# CAN_TOF.net
KiCad netlist of a schematic drawn in EAGLE
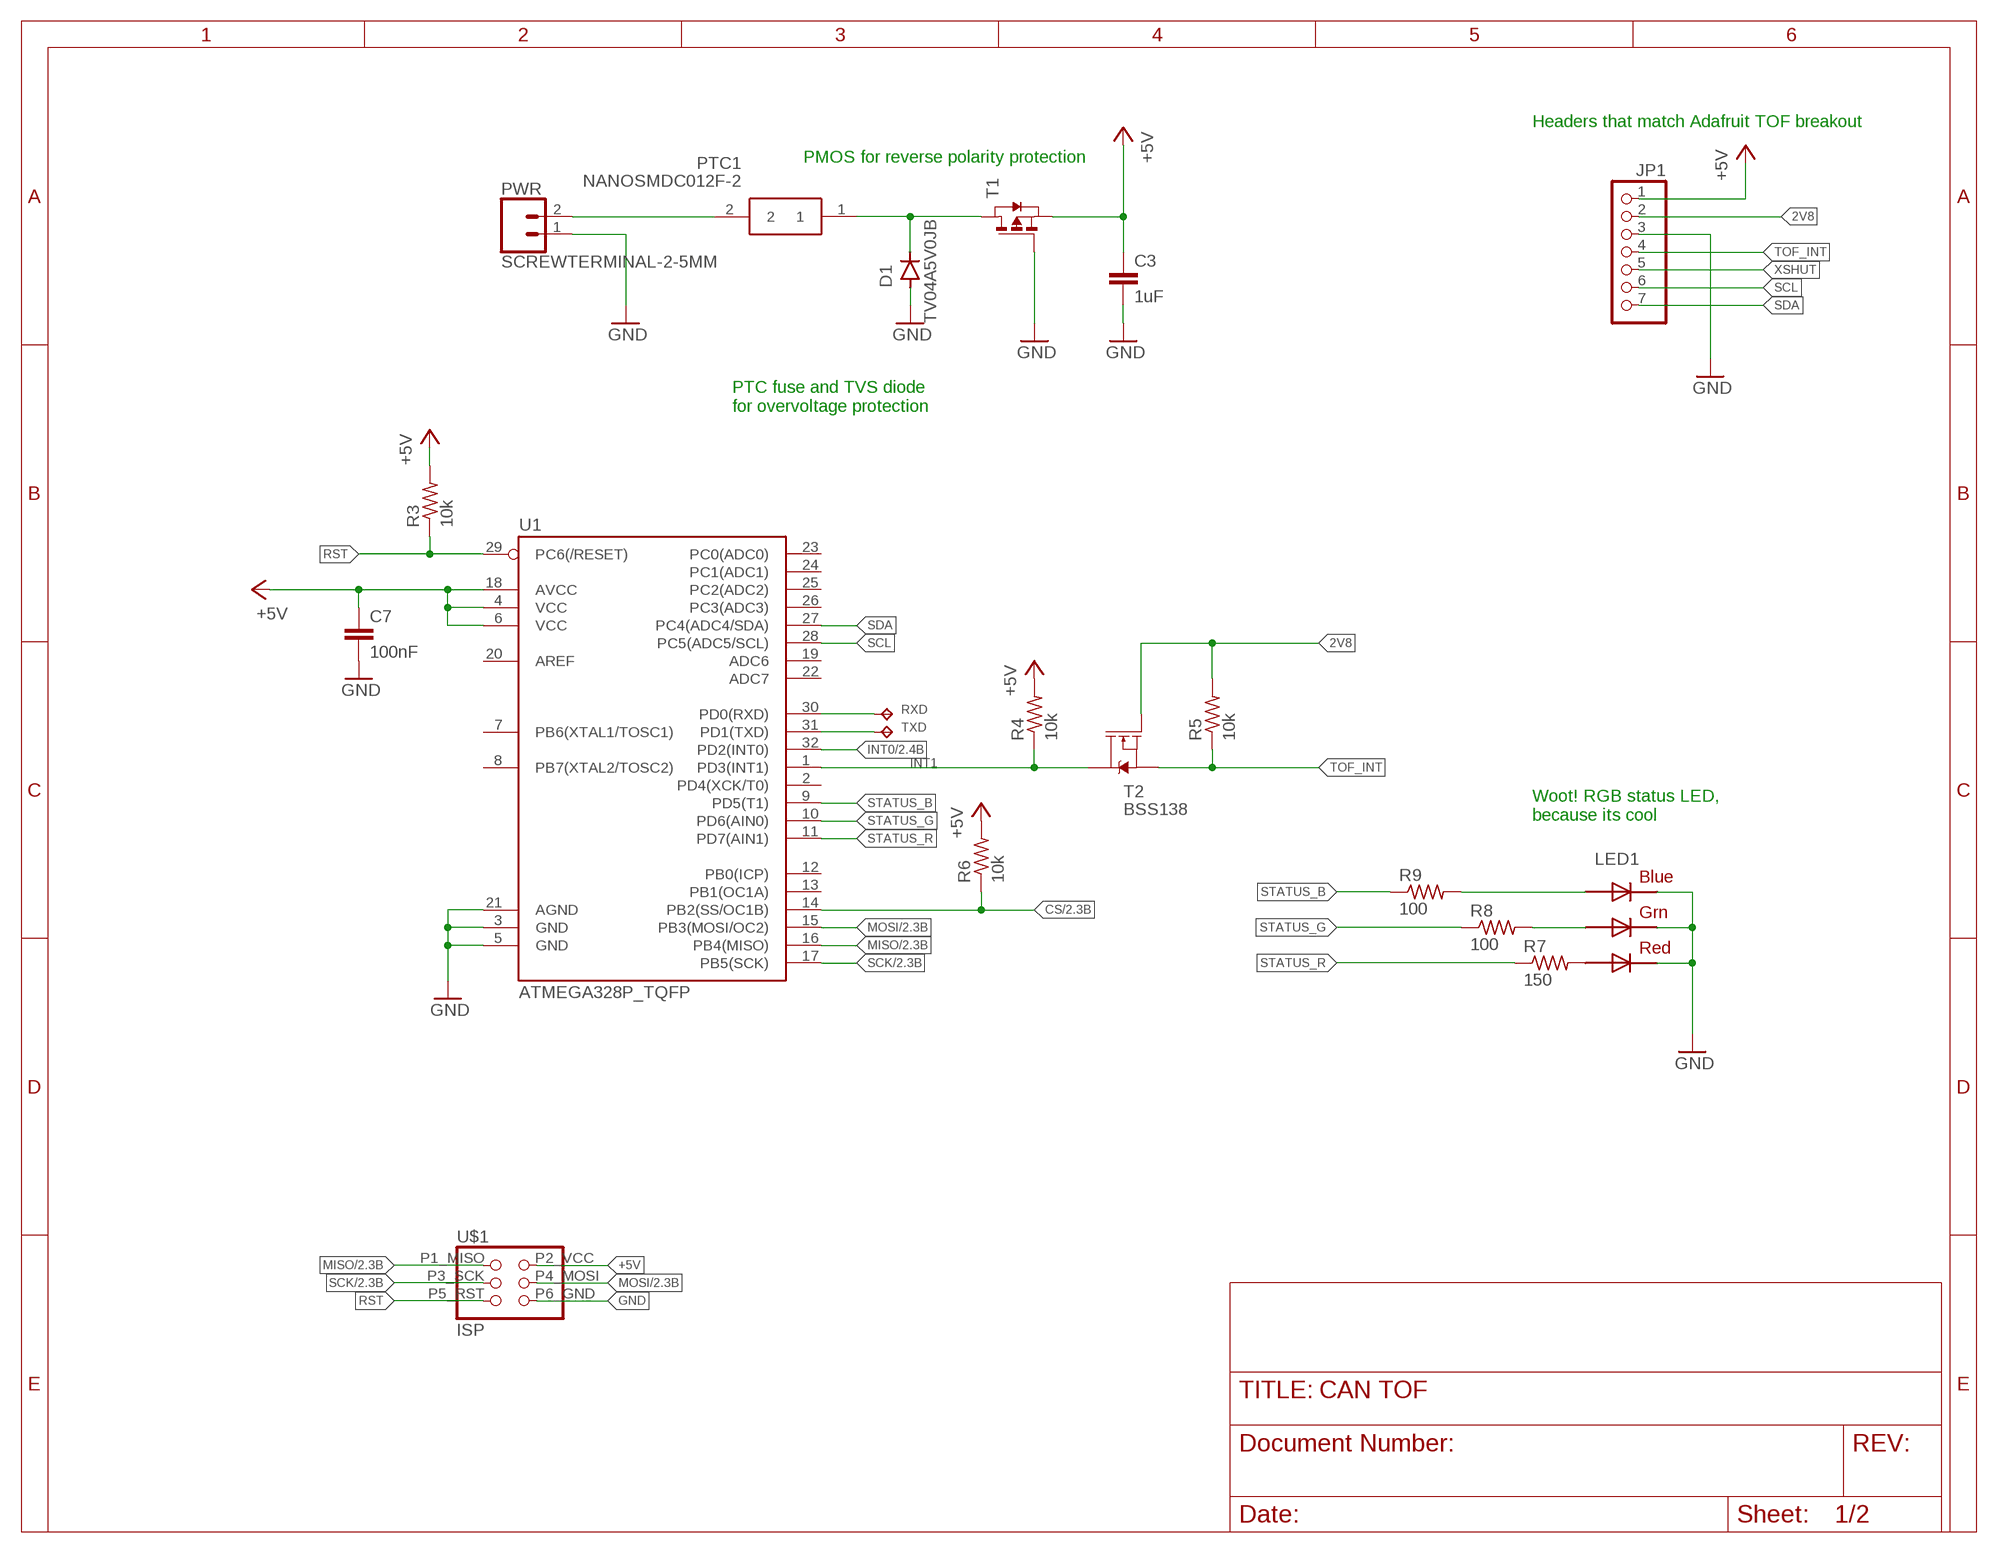
[diagram p0: schematic, sheet 1]
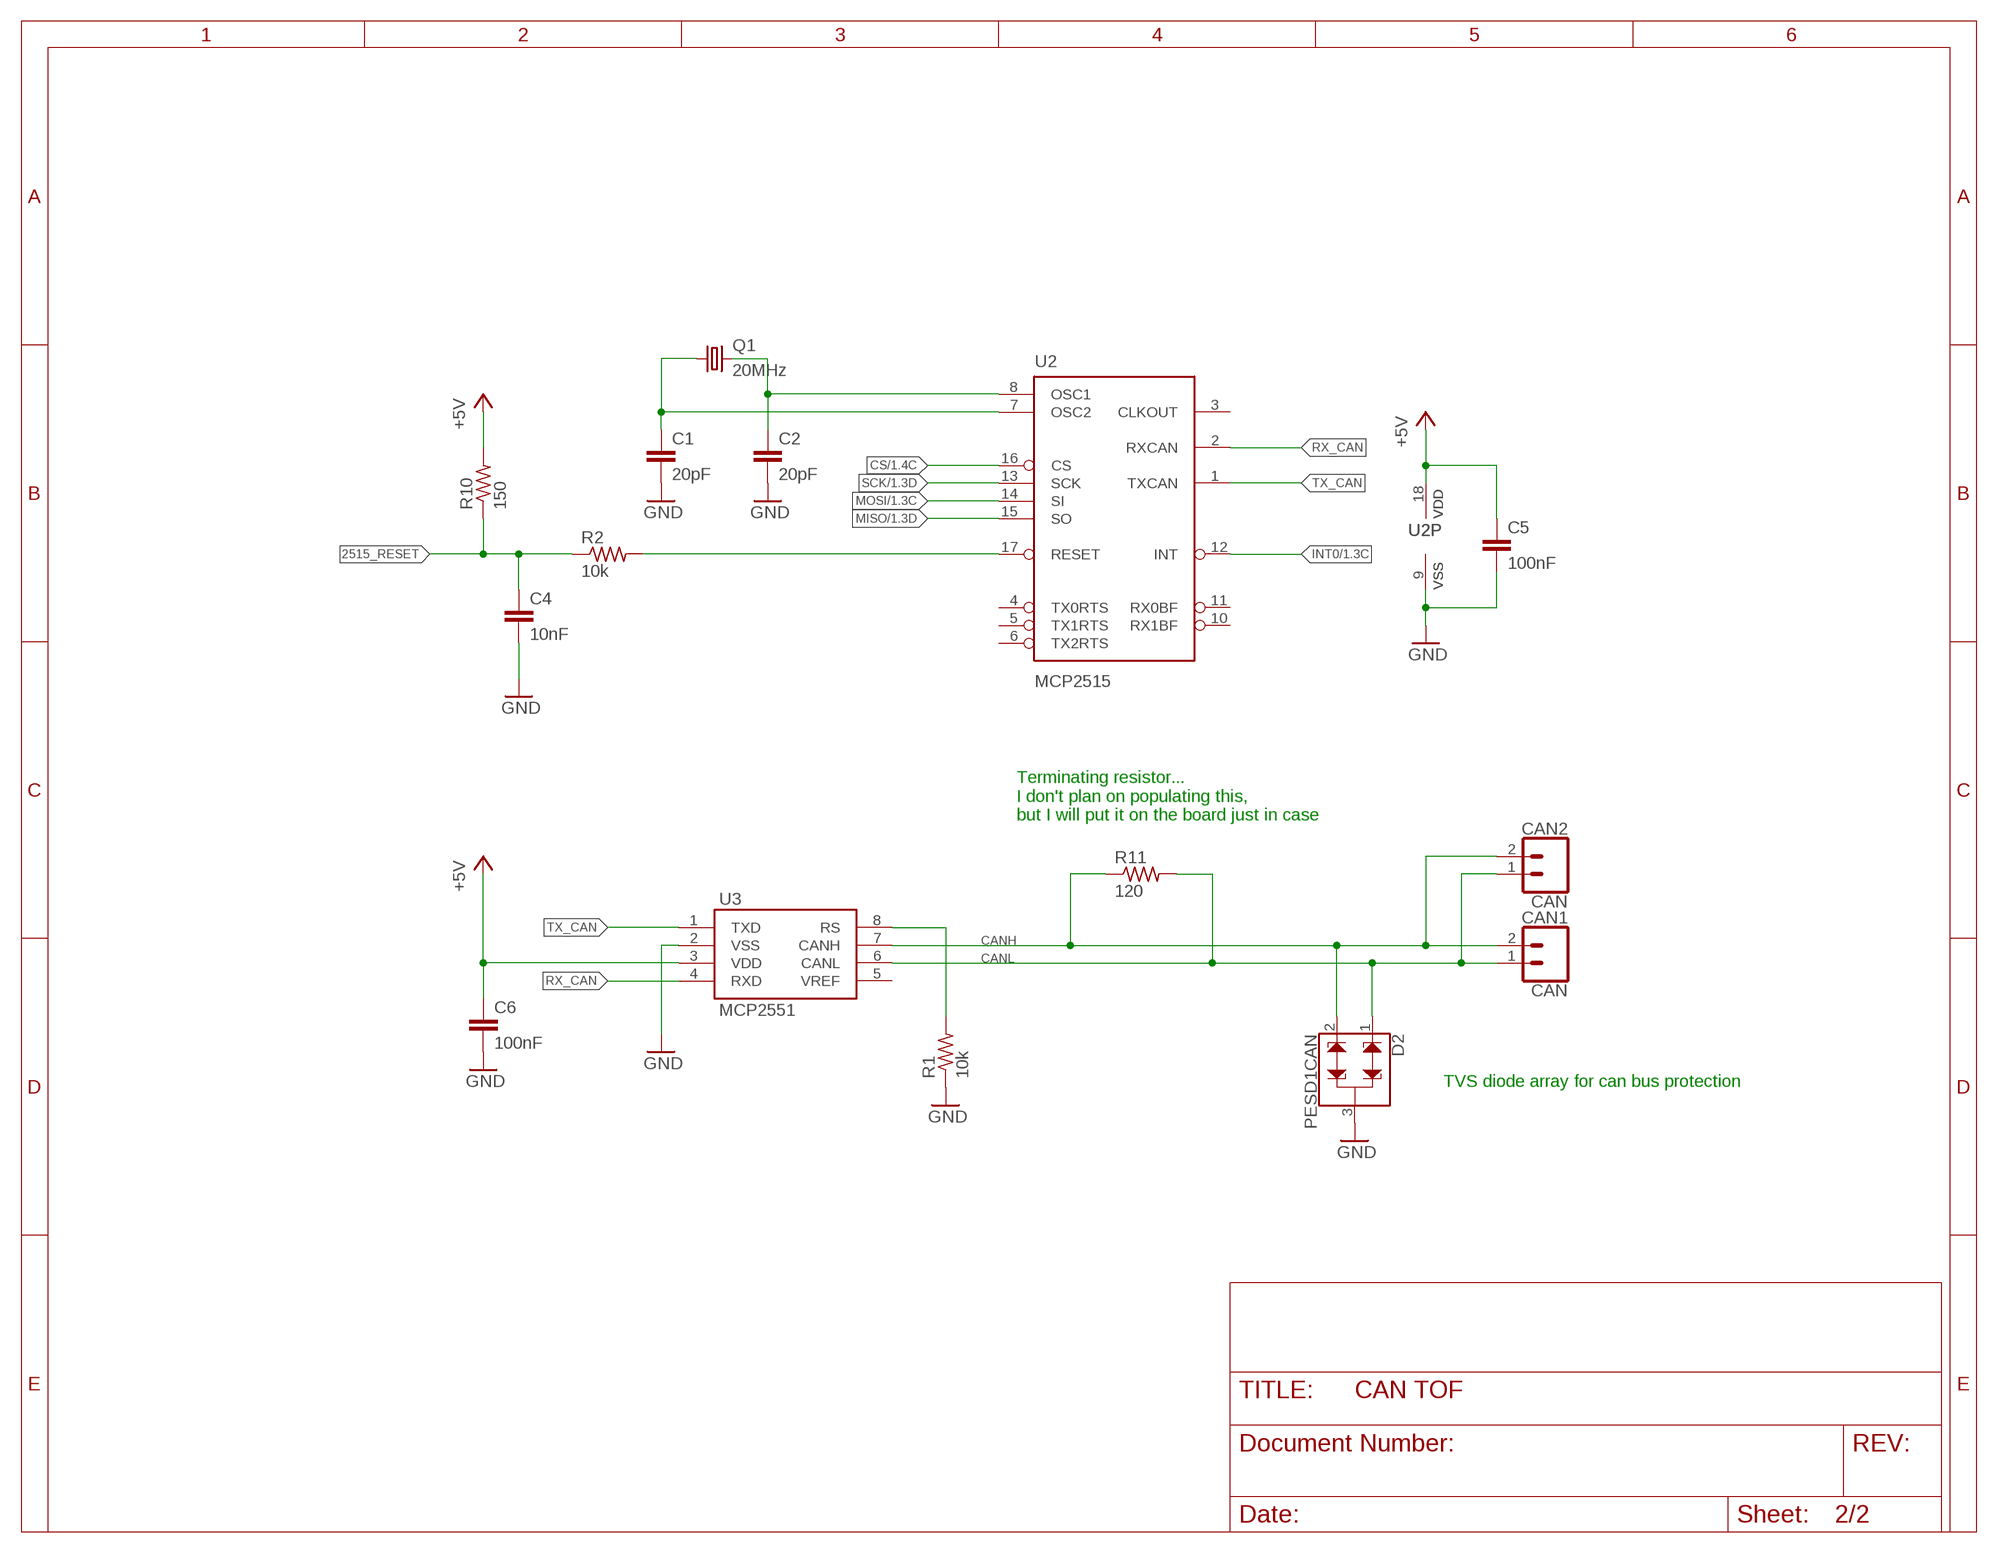
[diagram p1: schematic, sheet 2]

(export (version "E")
  (design (tool "Eeschema 10.0.6"))
  (components
    (comp (ref "C1")
      (value "20pF")
      (footprint "eagle-import:C0402")
      (libsource (lib "eagle-import") (part "C-EUC0402"))
    )
    (comp (ref "C2")
      (value "20pF")
      (footprint "eagle-import:C0402")
      (libsource (lib "eagle-import") (part "C-EUC0402"))
    )
    (comp (ref "C4")
      (value "10nF")
      (footprint "eagle-import:C0402")
      (libsource (lib "eagle-import") (part "C-EUC0402"))
    )
    (comp (ref "C5")
      (value "100nF")
      (footprint "eagle-import:C0402")
      (libsource (lib "eagle-import") (part "C-EUC0402"))
    )
    (comp (ref "C6")
      (value "100nF")
      (footprint "eagle-import:C0402")
      (libsource (lib "eagle-import") (part "C-EUC0402"))
    )
    (comp (ref "CAN1")
      (value "CAN")
      (footprint "eagle-import:SCREWTERMINAL-5MM-2")
      (libsource (lib "eagle-import") (part "SCREWTERMINAL-2-5MM"))
    )
    (comp (ref "CAN2")
      (value "CAN")
      (footprint "eagle-import:SCREWTERMINAL-5MM-2")
      (libsource (lib "eagle-import") (part "SCREWTERMINAL-2-5MM"))
    )
    (comp (ref "D2")
      (value "PESD1CAN")
      (footprint "eagle-import:SOT23-3")
      (libsource (lib "eagle-import") (part "PESD1CAN"))
    )
    (comp (ref "Q1")
      (value "20MHz")
      (footprint "eagle-import:CTS406")
      (libsource (lib "eagle-import") (part "CRYSTALCTS406"))
    )
    (comp (ref "R1")
      (value "10k")
      (footprint "eagle-import:R0805")
      (libsource (lib "eagle-import") (part "R-US_R0805"))
    )
    (comp (ref "R2")
      (value "10k")
      (footprint "eagle-import:R0805")
      (libsource (lib "eagle-import") (part "R-US_R0805"))
    )
    (comp (ref "R10")
      (value "150")
      (footprint "eagle-import:R0805")
      (libsource (lib "eagle-import") (part "R-US_R0805"))
    )
    (comp (ref "R11")
      (value "120")
      (footprint "eagle-import:R0805")
      (libsource (lib "eagle-import") (part "R-US_R0805"))
    )
    (comp (ref "U2")
      (value "MCP2515")
      (footprint "eagle-import:SO18W")
      (libsource (lib "eagle-import") (part "MCP2515(MCP2510)SO"))
    )
    (comp (ref "U3")
      (value "MCP2551")
      (footprint "eagle-import:SO08")
      (libsource (lib "eagle-import") (part "MCP2551"))
    )
    (comp (ref "C3")
      (value "1uF")
      (footprint "eagle-import:C0805")
      (libsource (lib "eagle-import") (part "C-EUC0805"))
    )
    (comp (ref "C7")
      (value "100nF")
      (footprint "eagle-import:C0402")
      (libsource (lib "eagle-import") (part "C-EUC0402"))
    )
    (comp (ref "D1")
      (value "TV04A5V0JB")
      (footprint "eagle-import:SMA-DO214AC")
      (libsource (lib "eagle-import") (part "GF1"))
    )
    (comp (ref "JP1")
      (value "PINHD-1X7")
      (footprint "eagle-import:1X07")
      (libsource (lib "eagle-import") (part "PINHD-1X7"))
    )
    (comp (ref "LED1")
      (value "RGBLED5050")
      (footprint "eagle-import:RGBLED5050")
      (libsource (lib "eagle-import") (part "RGBLED5050"))
    )
    (comp (ref "PTC1")
      (value "NANOSMDC012F-2")
      (footprint "eagle-import:FUSC3216X100N")
      (fields
        (field (name "MANUFACTURER_PART_NUMBER") "NANOSMDC010F-2")
        (field (name "MOUSER_PART_NUMBER") "650-NANOSMDC010F-2")
      )
      (libsource (lib "eagle-import") (part "NANOSMDC010F-2"))
    )
    (comp (ref "PWR")
      (value "SCREWTERMINAL-2-5MM")
      (footprint "eagle-import:SCREWTERMINAL-5MM-2")
      (libsource (lib "eagle-import") (part "SCREWTERMINAL-2-5MM"))
    )
    (comp (ref "R3")
      (value "10k")
      (footprint "eagle-import:R0805")
      (libsource (lib "eagle-import") (part "R-US_R0805"))
    )
    (comp (ref "R4")
      (value "10k")
      (footprint "eagle-import:R0805")
      (libsource (lib "eagle-import") (part "R-US_R0805"))
    )
    (comp (ref "R5")
      (value "10k")
      (footprint "eagle-import:R0805")
      (libsource (lib "eagle-import") (part "R-US_R0805"))
    )
    (comp (ref "R6")
      (value "10k")
      (footprint "eagle-import:R0805")
      (libsource (lib "eagle-import") (part "R-US_R0805"))
    )
    (comp (ref "R7")
      (value "150")
      (footprint "eagle-import:R0805")
      (libsource (lib "eagle-import") (part "R-US_R0805"))
    )
    (comp (ref "R8")
      (value "100")
      (footprint "eagle-import:R0805")
      (libsource (lib "eagle-import") (part "R-US_R0805"))
    )
    (comp (ref "R9")
      (value "100")
      (footprint "eagle-import:R0805")
      (libsource (lib "eagle-import") (part "R-US_R0805"))
    )
    (comp (ref "RXD")
      (value "TPB1,27")
      (footprint "eagle-import:B1,27")
      (libsource (lib "eagle-import") (part "TPB1,27"))
    )
    (comp (ref "T1")
      (value "PMOSSOT23")
      (footprint "eagle-import:SOT-23")
      (libsource (lib "eagle-import") (part "PMOSSOT23"))
    )
    (comp (ref "T2")
      (value "BSS138")
      (footprint "eagle-import:SOT23-3")
      (libsource (lib "eagle-import") (part "MOSFET-NCH-BSS138"))
    )
    (comp (ref "TXD")
      (value "TPB1,27")
      (footprint "eagle-import:B1,27")
      (libsource (lib "eagle-import") (part "TPB1,27"))
    )
    (comp (ref "U$1")
      (value "ISP")
      (footprint "eagle-import:ISP")
      (libsource (lib "eagle-import") (part "ISP"))
    )
    (comp (ref "U1")
      (value "ATMEGA328P_TQFP")
      (footprint "eagle-import:TQFP32-08")
      (libsource (lib "eagle-import") (part "ATMEGA328P_TQFP"))
    )
  )
  (nets
    (net (code "1") (name "+5V") (class "Default")
      (node (ref "C3") (pin "1") (pinfunction "1_1") (pintype "passive"))
      (node (ref "C5") (pin "1") (pinfunction "1_1") (pintype "passive"))
      (node (ref "C6") (pin "1") (pinfunction "1_1") (pintype "passive"))
      (node (ref "C7") (pin "1") (pinfunction "1_1") (pintype "passive"))
      (node (ref "JP1") (pin "1") (pinfunction "1_1") (pintype "passive"))
      (node (ref "R10") (pin "2") (pinfunction "2_2") (pintype "passive"))
      (node (ref "R3") (pin "2") (pinfunction "2_2") (pintype "passive"))
      (node (ref "R4") (pin "2") (pinfunction "2_2") (pintype "passive"))
      (node (ref "R6") (pin "2") (pinfunction "2_2") (pintype "passive"))
      (node (ref "T1") (pin "2") (pinfunction "S_2") (pintype "passive"))
      (node (ref "U$1") (pin "P2_VCC") (pinfunction "VCC_P2_VCC") (pintype "passive"))
      (node (ref "U1") (pin "18") (pinfunction "AVCC_18") (pintype "bidirectional"))
      (node (ref "U1") (pin "4") (pinfunction "VCC_4") (pintype "bidirectional"))
      (node (ref "U1") (pin "6") (pinfunction "VCC_6") (pintype "bidirectional"))
      (node (ref "U2") (pin "18") (pinfunction "VDD_18") (pintype "power_in"))
      (node (ref "U3") (pin "3") (pinfunction "VDD_3") (pintype "bidirectional"))
    )
    (net (code "2") (name "2V8") (class "Default")
      (node (ref "JP1") (pin "2") (pinfunction "2_2") (pintype "passive"))
      (node (ref "R5") (pin "2") (pinfunction "2_2") (pintype "passive"))
      (node (ref "T2") (pin "1") (pinfunction "G_1") (pintype "bidirectional"))
    )
    (net (code "3") (name "2515_RESET") (class "Default")
      (node (ref "C4") (pin "1") (pinfunction "1_1") (pintype "passive"))
      (node (ref "R10") (pin "1") (pinfunction "1_1") (pintype "passive"))
      (node (ref "R2") (pin "1") (pinfunction "1_1") (pintype "passive"))
    )
    (net (code "4") (name "CANH") (class "Default")
      (node (ref "CAN1") (pin "2") (pinfunction "2_2") (pintype "passive"))
      (node (ref "CAN2") (pin "2") (pinfunction "2_2") (pintype "passive"))
      (node (ref "D2") (pin "2") (pinfunction "2_2") (pintype "bidirectional"))
      (node (ref "R11") (pin "1") (pinfunction "1_1") (pintype "passive"))
      (node (ref "U3") (pin "7") (pinfunction "CANH_7") (pintype "bidirectional"))
    )
    (net (code "5") (name "CANL") (class "Default")
      (node (ref "CAN1") (pin "1") (pinfunction "1_1") (pintype "passive"))
      (node (ref "CAN2") (pin "1") (pinfunction "1_1") (pintype "passive"))
      (node (ref "D2") (pin "1") (pinfunction "1_1") (pintype "bidirectional"))
      (node (ref "R11") (pin "2") (pinfunction "2_2") (pintype "passive"))
      (node (ref "U3") (pin "6") (pinfunction "CANL_6") (pintype "bidirectional"))
    )
    (net (code "6") (name "CS") (class "Default")
      (node (ref "R6") (pin "1") (pinfunction "1_1") (pintype "passive"))
      (node (ref "U1") (pin "14") (pinfunction "PB2(SS/OC1B)_14") (pintype "bidirectional"))
      (node (ref "U2") (pin "16") (pinfunction "CS_16") (pintype "input"))
    )
    (net (code "7") (name "GND") (class "Default")
      (node (ref "C1") (pin "2") (pinfunction "2_2") (pintype "passive"))
      (node (ref "C2") (pin "2") (pinfunction "2_2") (pintype "passive"))
      (node (ref "C3") (pin "2") (pinfunction "2_2") (pintype "passive"))
      (node (ref "C4") (pin "2") (pinfunction "2_2") (pintype "passive"))
      (node (ref "C5") (pin "2") (pinfunction "2_2") (pintype "passive"))
      (node (ref "C6") (pin "2") (pinfunction "2_2") (pintype "passive"))
      (node (ref "C7") (pin "2") (pinfunction "2_2") (pintype "passive"))
      (node (ref "D1") (pin "A") (pinfunction "A_A") (pintype "passive"))
      (node (ref "D2") (pin "3") (pinfunction "3_3") (pintype "bidirectional"))
      (node (ref "JP1") (pin "3") (pinfunction "3_3") (pintype "passive"))
      (node (ref "LED1") (pin "4") (pinfunction "BLUE_C_4") (pintype "bidirectional"))
      (node (ref "LED1") (pin "5") (pinfunction "RED_C_5") (pintype "bidirectional"))
      (node (ref "LED1") (pin "6") (pinfunction "GREEN_C_6") (pintype "bidirectional"))
      (node (ref "PWR") (pin "1") (pinfunction "1_1") (pintype "passive"))
      (node (ref "R1") (pin "1") (pinfunction "1_1") (pintype "passive"))
      (node (ref "T1") (pin "3") (pinfunction "G_3") (pintype "passive"))
      (node (ref "U$1") (pin "P6_GND") (pinfunction "GND_P6_GND") (pintype "passive"))
      (node (ref "U1") (pin "21") (pinfunction "AGND_21") (pintype "bidirectional"))
      (node (ref "U1") (pin "3") (pinfunction "GND_3") (pintype "bidirectional"))
      (node (ref "U1") (pin "5") (pinfunction "GND_5") (pintype "bidirectional"))
      (node (ref "U2") (pin "9") (pinfunction "VSS_9") (pintype "power_in"))
      (node (ref "U3") (pin "2") (pinfunction "VSS_2") (pintype "bidirectional"))
    )
    (net (code "8") (name "INT0") (class "Default")
      (node (ref "U1") (pin "32") (pinfunction "PD2(INT0)_32") (pintype "bidirectional"))
      (node (ref "U2") (pin "12") (pinfunction "INT_12") (pintype "output"))
    )
    (net (code "9") (name "INT1") (class "Default")
      (node (ref "R4") (pin "1") (pinfunction "1_1") (pintype "passive"))
      (node (ref "T2") (pin "3") (pinfunction "D_3") (pintype "bidirectional"))
      (node (ref "U1") (pin "1") (pinfunction "PD3(INT1)_1") (pintype "bidirectional"))
    )
    (net (code "10") (name "MISO") (class "Default")
      (node (ref "U$1") (pin "P1_MISO") (pinfunction "MISO_P1_MISO") (pintype "passive"))
      (node (ref "U1") (pin "16") (pinfunction "PB4(MISO)_16") (pintype "bidirectional"))
      (node (ref "U2") (pin "15") (pinfunction "SO_15") (pintype "output"))
    )
    (net (code "11") (name "MOSI") (class "Default")
      (node (ref "U$1") (pin "P4_MOSI") (pinfunction "MOSI_P4_MOSI") (pintype "passive"))
      (node (ref "U1") (pin "15") (pinfunction "PB3(MOSI/OC2)_15") (pintype "bidirectional"))
      (node (ref "U2") (pin "14") (pinfunction "SI_14") (pintype "input"))
    )
    (net (code "12") (name "Net-(D1-C)") (class "Default")
      (node (ref "D1") (pin "K") (pinfunction "C_K") (pintype "passive"))
      (node (ref "PTC1") (pin "1") (pinfunction "1_1") (pintype "bidirectional"))
      (node (ref "T1") (pin "1") (pinfunction "D_1") (pintype "passive"))
    )
    (net (code "13") (name "Net-(LED1-BLUE_A)") (class "Default")
      (node (ref "LED1") (pin "3") (pinfunction "BLUE_A_3") (pintype "bidirectional"))
      (node (ref "R9") (pin "2") (pinfunction "2_2") (pintype "passive"))
    )
    (net (code "14") (name "Net-(LED1-GREEN_A)") (class "Default")
      (node (ref "LED1") (pin "1") (pinfunction "GREEN_A_1") (pintype "bidirectional"))
      (node (ref "R8") (pin "2") (pinfunction "2_2") (pintype "passive"))
    )
    (net (code "15") (name "Net-(LED1-RED_A)") (class "Default")
      (node (ref "LED1") (pin "2") (pinfunction "RED_A_2") (pintype "bidirectional"))
      (node (ref "R7") (pin "2") (pinfunction "2_2") (pintype "passive"))
    )
    (net (code "16") (name "Net-(PTC1-Pad2)") (class "Default")
      (node (ref "PTC1") (pin "2") (pinfunction "2_2") (pintype "bidirectional"))
      (node (ref "PWR") (pin "2") (pinfunction "2_2") (pintype "passive"))
    )
    (net (code "17") (name "Net-(Q1-2)") (class "Default")
      (node (ref "C2") (pin "1") (pinfunction "1_1") (pintype "passive"))
      (node (ref "Q1") (pin "3") (pinfunction "2_3") (pintype "passive"))
      (node (ref "U2") (pin "8") (pinfunction "OSC1_8") (pintype "input"))
    )
    (net (code "18") (name "Net-(U1-PD0(RXD))") (class "Default")
      (node (ref "RXD") (pin "TP") (pinfunction "TP_TP") (pintype "input"))
      (node (ref "U1") (pin "30") (pinfunction "PD0(RXD)_30") (pintype "bidirectional"))
    )
    (net (code "19") (name "Net-(U1-PD1(TXD))") (class "Default")
      (node (ref "TXD") (pin "TP") (pinfunction "TP_TP") (pintype "input"))
      (node (ref "U1") (pin "31") (pinfunction "PD1(TXD)_31") (pintype "bidirectional"))
    )
    (net (code "20") (name "Net-(U2A-OSC2)") (class "Default")
      (node (ref "C1") (pin "1") (pinfunction "1_1") (pintype "passive"))
      (node (ref "Q1") (pin "1") (pinfunction "1_1") (pintype "passive"))
      (node (ref "U2") (pin "7") (pinfunction "OSC2_7") (pintype "output"))
    )
    (net (code "21") (name "Net-(U2A-RESET)") (class "Default")
      (node (ref "R2") (pin "2") (pinfunction "2_2") (pintype "passive"))
      (node (ref "U2") (pin "17") (pinfunction "RESET_17") (pintype "input"))
    )
    (net (code "22") (name "Net-(U3-RS)") (class "Default")
      (node (ref "R1") (pin "2") (pinfunction "2_2") (pintype "passive"))
      (node (ref "U3") (pin "8") (pinfunction "RS_8") (pintype "bidirectional"))
    )
    (net (code "23") (name "RST") (class "Default")
      (node (ref "R3") (pin "1") (pinfunction "1_1") (pintype "passive"))
      (node (ref "U$1") (pin "P5_RST") (pinfunction "RST_P5_RST") (pintype "passive"))
      (node (ref "U1") (pin "29") (pinfunction "PC6(/RESET)_29") (pintype "bidirectional"))
    )
    (net (code "24") (name "RX_CAN") (class "Default")
      (node (ref "U2") (pin "2") (pinfunction "RXCAN_2") (pintype "input"))
      (node (ref "U3") (pin "4") (pinfunction "RXD_4") (pintype "bidirectional"))
    )
    (net (code "25") (name "SCK") (class "Default")
      (node (ref "U$1") (pin "P3_SCK") (pinfunction "SCK_P3_SCK") (pintype "passive"))
      (node (ref "U1") (pin "17") (pinfunction "PB5(SCK)_17") (pintype "bidirectional"))
      (node (ref "U2") (pin "13") (pinfunction "SCK_13") (pintype "input"))
    )
    (net (code "26") (name "SCL") (class "Default")
      (node (ref "JP1") (pin "6") (pinfunction "6_6") (pintype "passive"))
      (node (ref "U1") (pin "28") (pinfunction "PC5(ADC5/SCL)_28") (pintype "bidirectional"))
    )
    (net (code "27") (name "SDA") (class "Default")
      (node (ref "JP1") (pin "7") (pinfunction "7_7") (pintype "passive"))
      (node (ref "U1") (pin "27") (pinfunction "PC4(ADC4/SDA)_27") (pintype "bidirectional"))
    )
    (net (code "28") (name "STATUS_B") (class "Default")
      (node (ref "R9") (pin "1") (pinfunction "1_1") (pintype "passive"))
      (node (ref "U1") (pin "9") (pinfunction "PD5(T1)_9") (pintype "bidirectional"))
    )
    (net (code "29") (name "STATUS_G") (class "Default")
      (node (ref "R8") (pin "1") (pinfunction "1_1") (pintype "passive"))
      (node (ref "U1") (pin "10") (pinfunction "PD6(AIN0)_10") (pintype "bidirectional"))
    )
    (net (code "30") (name "STATUS_R") (class "Default")
      (node (ref "R7") (pin "1") (pinfunction "1_1") (pintype "passive"))
      (node (ref "U1") (pin "11") (pinfunction "PD7(AIN1)_11") (pintype "bidirectional"))
    )
    (net (code "31") (name "TOF_INT") (class "Default")
      (node (ref "JP1") (pin "4") (pinfunction "4_4") (pintype "passive"))
      (node (ref "R5") (pin "1") (pinfunction "1_1") (pintype "passive"))
      (node (ref "T2") (pin "2") (pinfunction "S_2") (pintype "bidirectional"))
    )
    (net (code "32") (name "TX_CAN") (class "Default")
      (node (ref "U2") (pin "1") (pinfunction "TXCAN_1") (pintype "output"))
      (node (ref "U3") (pin "1") (pinfunction "TXD_1") (pintype "bidirectional"))
    )
    (net (code "33") (name "XSHUT") (class "Default")
      (node (ref "JP1") (pin "5") (pinfunction "5_5") (pintype "passive"))
    )
    (net (code "34") (name "unconnected-(U1-ADC6-Pad19)") (class "Default")
      (node (ref "U1") (pin "19") (pinfunction "ADC6_19") (pintype "bidirectional"))
    )
    (net (code "35") (name "unconnected-(U1-ADC7-Pad22)") (class "Default")
      (node (ref "U1") (pin "22") (pinfunction "ADC7_22") (pintype "bidirectional"))
    )
    (net (code "36") (name "unconnected-(U1-AREF-Pad20)") (class "Default")
      (node (ref "U1") (pin "20") (pinfunction "AREF_20") (pintype "bidirectional"))
    )
    (net (code "37") (name "unconnected-(U1-PB0(ICP)-Pad12)") (class "Default")
      (node (ref "U1") (pin "12") (pinfunction "PB0(ICP)_12") (pintype "bidirectional"))
    )
    (net (code "38") (name "unconnected-(U1-PB1(OC1A)-Pad13)") (class "Default")
      (node (ref "U1") (pin "13") (pinfunction "PB1(OC1A)_13") (pintype "bidirectional"))
    )
    (net (code "39") (name "unconnected-(U1-PB6(XTAL1{slash}TOSC1)-Pad7)") (class "Default")
      (node (ref "U1") (pin "7") (pinfunction "PB6(XTAL1/TOSC1)_7") (pintype "bidirectional"))
    )
    (net (code "40") (name "unconnected-(U1-PB7(XTAL2{slash}TOSC2)-Pad8)") (class "Default")
      (node (ref "U1") (pin "8") (pinfunction "PB7(XTAL2/TOSC2)_8") (pintype "bidirectional"))
    )
    (net (code "41") (name "unconnected-(U1-PC0(ADC0)-Pad23)") (class "Default")
      (node (ref "U1") (pin "23") (pinfunction "PC0(ADC0)_23") (pintype "bidirectional"))
    )
    (net (code "42") (name "unconnected-(U1-PC1(ADC1)-Pad24)") (class "Default")
      (node (ref "U1") (pin "24") (pinfunction "PC1(ADC1)_24") (pintype "bidirectional"))
    )
    (net (code "43") (name "unconnected-(U1-PC2(ADC2)-Pad25)") (class "Default")
      (node (ref "U1") (pin "25") (pinfunction "PC2(ADC2)_25") (pintype "bidirectional"))
    )
    (net (code "44") (name "unconnected-(U1-PC3(ADC3)-Pad26)") (class "Default")
      (node (ref "U1") (pin "26") (pinfunction "PC3(ADC3)_26") (pintype "bidirectional"))
    )
    (net (code "45") (name "unconnected-(U1-PD4(XCK{slash}T0)-Pad2)") (class "Default")
      (node (ref "U1") (pin "2") (pinfunction "PD4(XCK/T0)_2") (pintype "bidirectional"))
    )
    (net (code "46") (name "unconnected-(U2A-CLKOUT-Pad3)") (class "Default")
      (node (ref "U2") (pin "3") (pinfunction "CLKOUT_3") (pintype "output"))
    )
    (net (code "47") (name "unconnected-(U2A-RX0BF-Pad11)") (class "Default")
      (node (ref "U2") (pin "11") (pinfunction "RX0BF_11") (pintype "output"))
    )
    (net (code "48") (name "unconnected-(U2A-RX1BF-Pad10)") (class "Default")
      (node (ref "U2") (pin "10") (pinfunction "RX1BF_10") (pintype "output"))
    )
    (net (code "49") (name "unconnected-(U2A-TX0RTS-Pad4)") (class "Default")
      (node (ref "U2") (pin "4") (pinfunction "TX0RTS_4") (pintype "input"))
    )
    (net (code "50") (name "unconnected-(U2A-TX1RTS-Pad5)") (class "Default")
      (node (ref "U2") (pin "5") (pinfunction "TX1RTS_5") (pintype "input"))
    )
    (net (code "51") (name "unconnected-(U2A-TX2RTS-Pad6)") (class "Default")
      (node (ref "U2") (pin "6") (pinfunction "TX2RTS_6") (pintype "input"))
    )
    (net (code "52") (name "unconnected-(U3-VREF-Pad5)") (class "Default")
      (node (ref "U3") (pin "5") (pinfunction "VREF_5") (pintype "bidirectional"))
    )
  )
)
